# 07_-_Sensors.net
KiCad netlist of a schematic drawn in Altium Designer
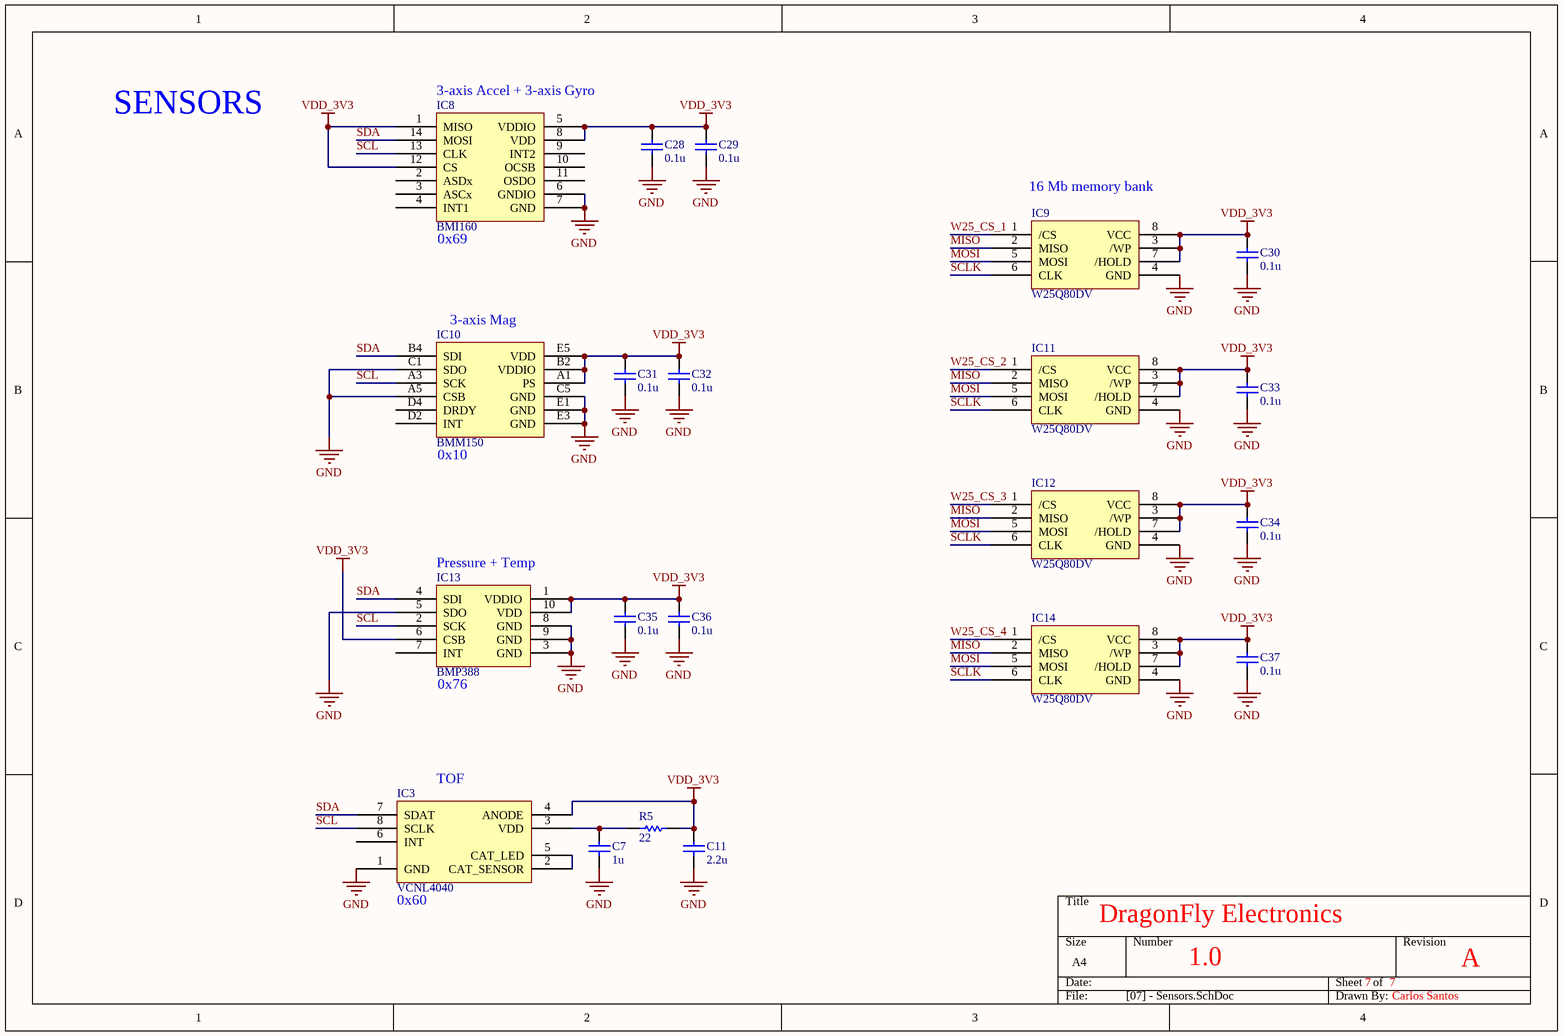
[diagram p0: [07] - Sensors.SchDoc]

(export (version "E")
  (design (tool "Eeschema 10.0.6"))
  (components
    (comp (ref "C7")
      (value "1u")
      (footprint "0402 - Capacitor")
      (fields (field (name "Comment") "Capacitor"))
      (libsource (lib "Mine") (part "Capacitor"))
    )
    (comp (ref "C11")
      (value "2.2u")
      (footprint "0402 - Capacitor")
      (fields (field (name "Comment") "Capacitor"))
      (libsource (lib "Mine") (part "Capacitor"))
    )
    (comp (ref "C28")
      (value "0.1u")
      (footprint "0402 - Capacitor")
      (fields (field (name "Comment") "Capacitor"))
      (libsource (lib "Mine") (part "Capacitor"))
    )
    (comp (ref "C29")
      (value "0.1u")
      (footprint "0402 - Capacitor")
      (fields (field (name "Comment") "Capacitor"))
      (libsource (lib "Mine") (part "Capacitor"))
    )
    (comp (ref "C30")
      (value "0.1u")
      (footprint "0402 - Capacitor")
      (fields (field (name "Comment") "Capacitor"))
      (libsource (lib "Mine") (part "Capacitor"))
    )
    (comp (ref "C31")
      (value "0.1u")
      (footprint "0402 - Capacitor")
      (fields (field (name "Comment") "Capacitor"))
      (libsource (lib "Mine") (part "Capacitor"))
    )
    (comp (ref "C32")
      (value "0.1u")
      (footprint "0402 - Capacitor")
      (fields (field (name "Comment") "Capacitor"))
      (libsource (lib "Mine") (part "Capacitor"))
    )
    (comp (ref "C33")
      (value "0.1u")
      (footprint "0402 - Capacitor")
      (fields (field (name "Comment") "Capacitor"))
      (libsource (lib "Mine") (part "Capacitor"))
    )
    (comp (ref "C34")
      (value "0.1u")
      (footprint "0402 - Capacitor")
      (fields (field (name "Comment") "Capacitor"))
      (libsource (lib "Mine") (part "Capacitor"))
    )
    (comp (ref "C35")
      (value "0.1u")
      (footprint "0402 - Capacitor")
      (fields (field (name "Comment") "Capacitor"))
      (libsource (lib "Mine") (part "Capacitor"))
    )
    (comp (ref "C36")
      (value "0.1u")
      (footprint "0402 - Capacitor")
      (fields (field (name "Comment") "Capacitor"))
      (libsource (lib "Mine") (part "Capacitor"))
    )
    (comp (ref "C37")
      (value "0.1u")
      (footprint "0402 - Capacitor")
      (fields (field (name "Comment") "Capacitor"))
      (libsource (lib "Mine") (part "Capacitor"))
    )
    (comp (ref "IC3")
      (value "VCNL4040")
      (footprint "VCNL4040M3OE")
      (fields (field (name "DIGIKEY PART #") "VCNL4040M3OECT-ND"))
      (libsource (lib "Mine") (part "VCNL4040"))
    )
    (comp (ref "IC8")
      (value "BMI160")
      (footprint "BMI160")
      (fields (field (name "DIGIKEY PART #") "828-1057-1-ND"))
      (libsource (lib "Mine") (part "BMI160"))
    )
    (comp (ref "IC9")
      (value "W25Q80DV")
      (footprint "8 - Pad USON 2x3mm")
      (fields (field (name "DIGIKEY PART #") "W25Q80DVUXIECT-ND"))
      (libsource (lib "Mine") (part "W25X20CL"))
    )
    (comp (ref "IC10")
      (value "BMM150")
      (footprint "BMM150")
      (fields (field (name "DIGIKEY PART #") "828-1044-1-ND"))
      (libsource (lib "Mine") (part "BMM150"))
    )
    (comp (ref "IC11")
      (value "W25Q80DV")
      (footprint "8 - Pad USON 2x3mm")
      (fields (field (name "DIGIKEY PART #") "W25Q80DVUXIECT-ND"))
      (libsource (lib "Mine") (part "W25X20CL"))
    )
    (comp (ref "IC12")
      (value "W25Q80DV")
      (footprint "8 - Pad USON 2x3mm")
      (fields (field (name "DIGIKEY PART #") "W25Q80DVUXIECT-ND"))
      (libsource (lib "Mine") (part "W25X20CL"))
    )
    (comp (ref "IC13")
      (value "BMP388")
      (footprint "BMP388")
      (fields (field (name "DIGIKEY PART #") "828-1079-1-ND"))
      (libsource (lib "Mine") (part "BMP388"))
    )
    (comp (ref "IC14")
      (value "W25Q80DV")
      (footprint "8 - Pad USON 2x3mm")
      (fields (field (name "DIGIKEY PART #") "W25Q80DVUXIECT-ND"))
      (libsource (lib "Mine") (part "W25X20CL"))
    )
    (comp (ref "R5")
      (value "22")
      (footprint "0402 - Resistor")
      (fields (field (name "Comment") "Resistor"))
      (libsource (lib "Mine") (part "Resistor"))
    )
  )
  (nets
    (net (code "1") (name "/MISO") (class "Default")
      (node (ref "IC11") (pin "2") (pinfunction "MISO_2") (pintype "passive"))
      (node (ref "IC12") (pin "2") (pinfunction "MISO_2") (pintype "passive"))
      (node (ref "IC14") (pin "2") (pinfunction "MISO_2") (pintype "passive"))
      (node (ref "IC9") (pin "2") (pinfunction "MISO_2") (pintype "passive"))
    )
    (net (code "2") (name "/MOSI") (class "Default")
      (node (ref "IC11") (pin "5") (pinfunction "MOSI_5") (pintype "passive"))
      (node (ref "IC12") (pin "5") (pinfunction "MOSI_5") (pintype "passive"))
      (node (ref "IC14") (pin "5") (pinfunction "MOSI_5") (pintype "passive"))
      (node (ref "IC9") (pin "5") (pinfunction "MOSI_5") (pintype "passive"))
    )
    (net (code "3") (name "/SCL") (class "Default")
      (node (ref "IC10") (pin "A3") (pinfunction "SCK_A3") (pintype "passive"))
      (node (ref "IC13") (pin "2") (pinfunction "SCK_2") (pintype "passive"))
      (node (ref "IC3") (pin "8") (pinfunction "SCLK_8") (pintype "passive"))
      (node (ref "IC8") (pin "13") (pinfunction "CLK_13") (pintype "passive"))
    )
    (net (code "4") (name "/SCLK") (class "Default")
      (node (ref "IC11") (pin "6") (pinfunction "CLK_6") (pintype "passive"))
      (node (ref "IC12") (pin "6") (pinfunction "CLK_6") (pintype "passive"))
      (node (ref "IC14") (pin "6") (pinfunction "CLK_6") (pintype "passive"))
      (node (ref "IC9") (pin "6") (pinfunction "CLK_6") (pintype "passive"))
    )
    (net (code "5") (name "/SDA") (class "Default")
      (node (ref "IC10") (pin "B4") (pinfunction "SDI_B4") (pintype "passive"))
      (node (ref "IC13") (pin "4") (pinfunction "SDI_4") (pintype "passive"))
      (node (ref "IC3") (pin "7") (pinfunction "SDAT_7") (pintype "passive"))
      (node (ref "IC8") (pin "14") (pinfunction "MOSI_14") (pintype "passive"))
    )
    (net (code "6") (name "/W25_CS_1") (class "Default")
      (node (ref "IC9") (pin "1") (pinfunction "/CS_1") (pintype "passive"))
    )
    (net (code "7") (name "/W25_CS_2") (class "Default")
      (node (ref "IC11") (pin "1") (pinfunction "/CS_1") (pintype "passive"))
    )
    (net (code "8") (name "/W25_CS_3") (class "Default")
      (node (ref "IC12") (pin "1") (pinfunction "/CS_1") (pintype "passive"))
    )
    (net (code "9") (name "/W25_CS_4") (class "Default")
      (node (ref "IC14") (pin "1") (pinfunction "/CS_1") (pintype "passive"))
    )
    (net (code "10") (name "GND") (class "Default")
      (node (ref "C11") (pin "1") (pinfunction "1_1") (pintype "passive"))
      (node (ref "C28") (pin "1") (pinfunction "1_1") (pintype "passive"))
      (node (ref "C29") (pin "1") (pinfunction "1_1") (pintype "passive"))
      (node (ref "C30") (pin "1") (pinfunction "1_1") (pintype "passive"))
      (node (ref "C31") (pin "1") (pinfunction "1_1") (pintype "passive"))
      (node (ref "C32") (pin "1") (pinfunction "1_1") (pintype "passive"))
      (node (ref "C33") (pin "1") (pinfunction "1_1") (pintype "passive"))
      (node (ref "C34") (pin "1") (pinfunction "1_1") (pintype "passive"))
      (node (ref "C35") (pin "1") (pinfunction "1_1") (pintype "passive"))
      (node (ref "C36") (pin "1") (pinfunction "1_1") (pintype "passive"))
      (node (ref "C37") (pin "1") (pinfunction "1_1") (pintype "passive"))
      (node (ref "C7") (pin "1") (pinfunction "1_1") (pintype "passive"))
      (node (ref "IC10") (pin "A5") (pinfunction "CSB_A5") (pintype "passive"))
      (node (ref "IC10") (pin "C1") (pinfunction "SDO_C1") (pintype "passive"))
      (node (ref "IC10") (pin "C5") (pinfunction "GND_C5") (pintype "passive"))
      (node (ref "IC10") (pin "E1") (pinfunction "GND_E1") (pintype "passive"))
      (node (ref "IC10") (pin "E3") (pinfunction "GND_E3") (pintype "passive"))
      (node (ref "IC11") (pin "4") (pinfunction "GND_4") (pintype "passive"))
      (node (ref "IC12") (pin "4") (pinfunction "GND_4") (pintype "passive"))
      (node (ref "IC13") (pin "3") (pinfunction "GND_3") (pintype "passive"))
      (node (ref "IC13") (pin "5") (pinfunction "SDO_5") (pintype "passive"))
      (node (ref "IC13") (pin "8") (pinfunction "GND_8") (pintype "passive"))
      (node (ref "IC13") (pin "9") (pinfunction "GND_9") (pintype "passive"))
      (node (ref "IC14") (pin "4") (pinfunction "GND_4") (pintype "passive"))
      (node (ref "IC3") (pin "1") (pinfunction "GND_1") (pintype "passive"))
      (node (ref "IC8") (pin "6") (pinfunction "GNDIO_6") (pintype "passive"))
      (node (ref "IC8") (pin "7") (pinfunction "GND_7") (pintype "passive"))
      (node (ref "IC9") (pin "4") (pinfunction "GND_4") (pintype "passive"))
    )
    (net (code "11") (name "Net-(IC3-CAT_LED)") (class "Default")
      (node (ref "IC3") (pin "2") (pinfunction "CAT_SENSOR_2") (pintype "passive"))
      (node (ref "IC3") (pin "5") (pinfunction "CAT_LED_5") (pintype "passive"))
    )
    (net (code "12") (name "Net-(IC3-VDD)") (class "Default")
      (node (ref "C7") (pin "2") (pinfunction "2_2") (pintype "passive"))
      (node (ref "IC3") (pin "3") (pinfunction "VDD_3") (pintype "passive"))
      (node (ref "R5") (pin "1") (pinfunction "1_1") (pintype "passive"))
    )
    (net (code "13") (name "VDD_3V3") (class "Default")
      (node (ref "C11") (pin "2") (pinfunction "2_2") (pintype "passive"))
      (node (ref "C28") (pin "2") (pinfunction "2_2") (pintype "passive"))
      (node (ref "C29") (pin "2") (pinfunction "2_2") (pintype "passive"))
      (node (ref "C30") (pin "2") (pinfunction "2_2") (pintype "passive"))
      (node (ref "C31") (pin "2") (pinfunction "2_2") (pintype "passive"))
      (node (ref "C32") (pin "2") (pinfunction "2_2") (pintype "passive"))
      (node (ref "C33") (pin "2") (pinfunction "2_2") (pintype "passive"))
      (node (ref "C34") (pin "2") (pinfunction "2_2") (pintype "passive"))
      (node (ref "C35") (pin "2") (pinfunction "2_2") (pintype "passive"))
      (node (ref "C36") (pin "2") (pinfunction "2_2") (pintype "passive"))
      (node (ref "C37") (pin "2") (pinfunction "2_2") (pintype "passive"))
      (node (ref "IC10") (pin "A1") (pinfunction "PS_A1") (pintype "passive"))
      (node (ref "IC10") (pin "B2") (pinfunction "VDDIO_B2") (pintype "passive"))
      (node (ref "IC10") (pin "E5") (pinfunction "VDD_E5") (pintype "passive"))
      (node (ref "IC11") (pin "3") (pinfunction "/WP_3") (pintype "passive"))
      (node (ref "IC11") (pin "7") (pinfunction "/HOLD_7") (pintype "passive"))
      (node (ref "IC11") (pin "8") (pinfunction "VCC_8") (pintype "passive"))
      (node (ref "IC12") (pin "3") (pinfunction "/WP_3") (pintype "passive"))
      (node (ref "IC12") (pin "7") (pinfunction "/HOLD_7") (pintype "passive"))
      (node (ref "IC12") (pin "8") (pinfunction "VCC_8") (pintype "passive"))
      (node (ref "IC13") (pin "1") (pinfunction "VDDIO_1") (pintype "passive"))
      (node (ref "IC13") (pin "10") (pinfunction "VDD_10") (pintype "passive"))
      (node (ref "IC13") (pin "6") (pinfunction "CSB_6") (pintype "passive"))
      (node (ref "IC14") (pin "3") (pinfunction "/WP_3") (pintype "passive"))
      (node (ref "IC14") (pin "7") (pinfunction "/HOLD_7") (pintype "passive"))
      (node (ref "IC14") (pin "8") (pinfunction "VCC_8") (pintype "passive"))
      (node (ref "IC3") (pin "4") (pinfunction "ANODE_4") (pintype "passive"))
      (node (ref "IC8") (pin "1") (pinfunction "MISO_1") (pintype "passive"))
      (node (ref "IC8") (pin "12") (pinfunction "CS_12") (pintype "passive"))
      (node (ref "IC8") (pin "5") (pinfunction "VDDIO_5") (pintype "passive"))
      (node (ref "IC8") (pin "8") (pinfunction "VDD_8") (pintype "passive"))
      (node (ref "IC9") (pin "3") (pinfunction "/WP_3") (pintype "passive"))
      (node (ref "IC9") (pin "7") (pinfunction "/HOLD_7") (pintype "passive"))
      (node (ref "IC9") (pin "8") (pinfunction "VCC_8") (pintype "passive"))
      (node (ref "R5") (pin "2") (pinfunction "2_2") (pintype "passive"))
    )
    (net (code "14") (name "unconnected-(IC3-INT-Pad6)") (class "Default")
      (node (ref "IC3") (pin "6") (pinfunction "INT_6") (pintype "passive"))
    )
    (net (code "15") (name "unconnected-(IC8-ASCx-Pad3)") (class "Default")
      (node (ref "IC8") (pin "3") (pinfunction "ASCx_3") (pintype "passive"))
    )
    (net (code "16") (name "unconnected-(IC8-ASDx-Pad2)") (class "Default")
      (node (ref "IC8") (pin "2") (pinfunction "ASDx_2") (pintype "passive"))
    )
    (net (code "17") (name "unconnected-(IC8-INT1-Pad4)") (class "Default")
      (node (ref "IC8") (pin "4") (pinfunction "INT1_4") (pintype "passive"))
    )
    (net (code "18") (name "unconnected-(IC8-INT2-Pad9)") (class "Default")
      (node (ref "IC8") (pin "9") (pinfunction "INT2_9") (pintype "passive"))
    )
    (net (code "19") (name "unconnected-(IC8-OCSB-Pad10)") (class "Default")
      (node (ref "IC8") (pin "10") (pinfunction "OCSB_10") (pintype "passive"))
    )
    (net (code "20") (name "unconnected-(IC8-OSDO-Pad11)") (class "Default")
      (node (ref "IC8") (pin "11") (pinfunction "OSDO_11") (pintype "passive"))
    )
    (net (code "21") (name "unconnected-(IC10-DRDY-PadD4)") (class "Default")
      (node (ref "IC10") (pin "D4") (pinfunction "DRDY_D4") (pintype "passive"))
    )
    (net (code "22") (name "unconnected-(IC10-INT-PadD2)") (class "Default")
      (node (ref "IC10") (pin "D2") (pinfunction "INT_D2") (pintype "passive"))
    )
    (net (code "23") (name "unconnected-(IC13-INT-Pad7)") (class "Default")
      (node (ref "IC13") (pin "7") (pinfunction "INT_7") (pintype "passive"))
    )
  )
)
